# SkateInfoView.net
KiCad netlist of a schematic drawn in Altium Designer
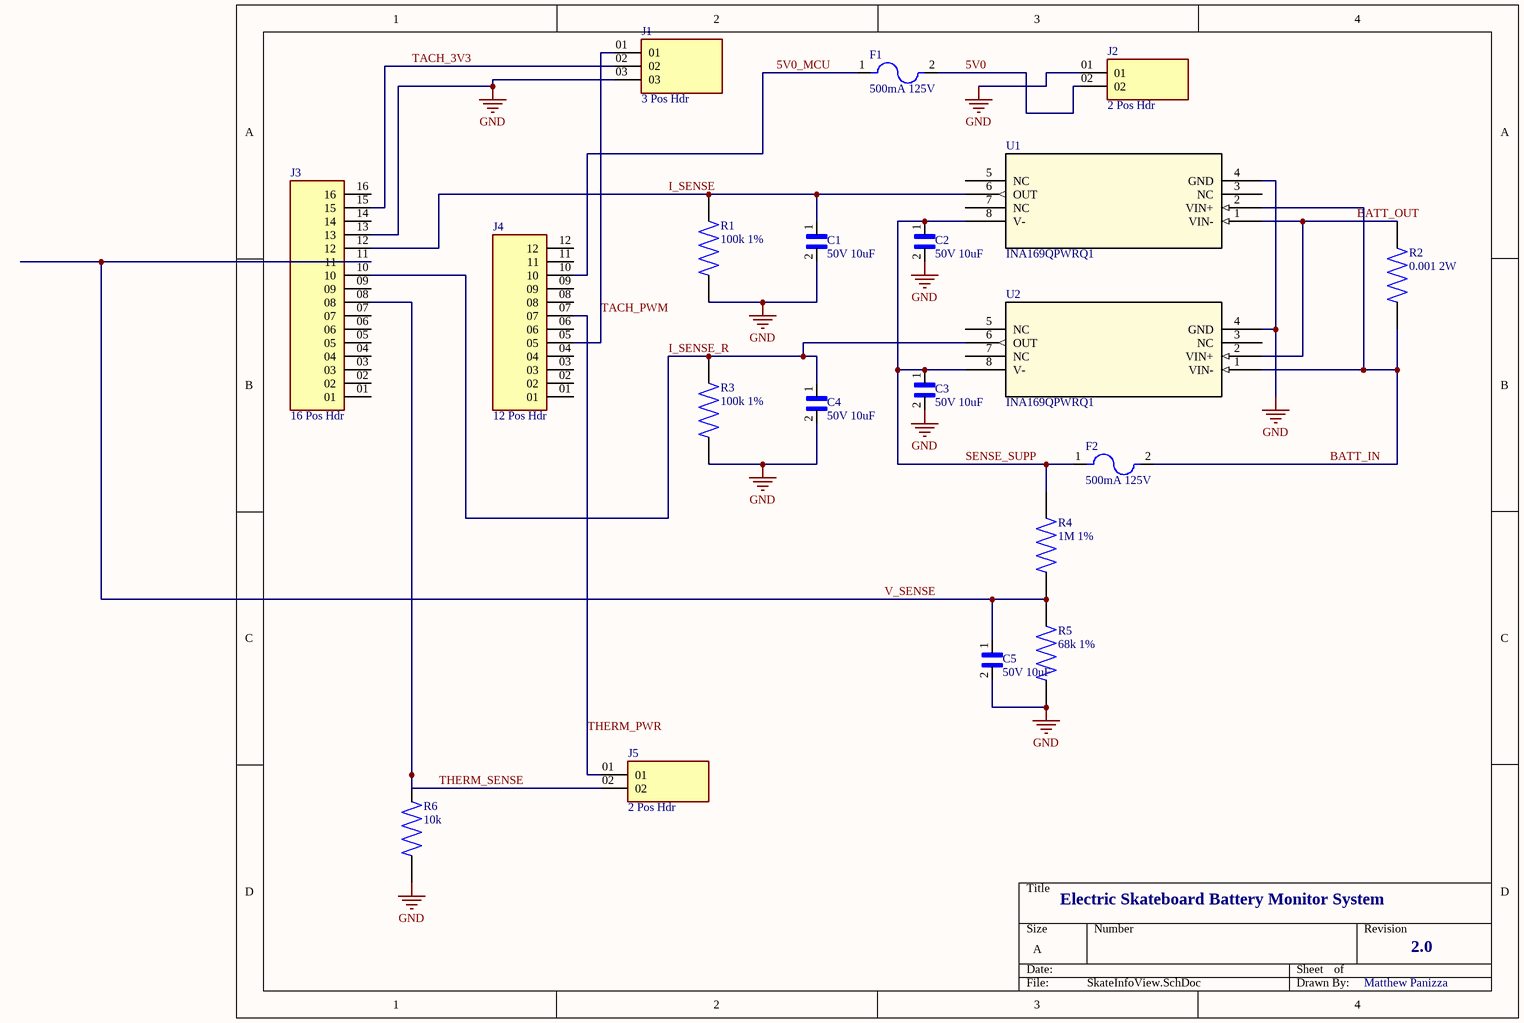
[diagram p0: SkateInfoView.SchDoc]

(export (version "E")
  (design (tool "Eeschema 10.0.6"))
  (components
    (comp (ref "C1")
      (value "50V 10uF")
      (footprint "GRT31CR61H106ME01L:CAP3216X125N")
      (description "1206 10 uF 50 V Â±20% Tolerance X5R Multilayer Ceramic Capacitor")
      (fields
        (field (name "MP") "GRT31CR61H106ME01L")
        (field (name "MF") "{'manufacturer': u'Murata Electronics'}")
      )
      (libsource (lib "GRT31CR61H106ME01L") (part "GRT31CR61H106ME01L"))
    )
    (comp (ref "C2")
      (value "50V 10uF")
      (footprint "GRT31CR61H106ME01L:CAP3216X125N")
      (description "1206 10 uF 50 V Â±20% Tolerance X5R Multilayer Ceramic Capacitor")
      (fields
        (field (name "MP") "GRT31CR61H106ME01L")
        (field (name "MF") "{'manufacturer': u'Murata Electronics'}")
      )
      (libsource (lib "GRT31CR61H106ME01L") (part "GRT31CR61H106ME01L"))
    )
    (comp (ref "C3")
      (value "50V 10uF")
      (footprint "GRT31CR61H106ME01L:CAP3216X125N")
      (description "1206 10 uF 50 V Â±20% Tolerance X5R Multilayer Ceramic Capacitor")
      (fields
        (field (name "MP") "GRT31CR61H106ME01L")
        (field (name "MF") "{'manufacturer': u'Murata Electronics'}")
      )
      (libsource (lib "GRT31CR61H106ME01L") (part "GRT31CR61H106ME01L"))
    )
    (comp (ref "C4")
      (value "50V 10uF")
      (footprint "GRT31CR61H106ME01L:CAP3216X125N")
      (description "1206 10 uF 50 V Â±20% Tolerance X5R Multilayer Ceramic Capacitor")
      (fields
        (field (name "MP") "GRT31CR61H106ME01L")
        (field (name "MF") "{'manufacturer': u'Murata Electronics'}")
      )
      (libsource (lib "GRT31CR61H106ME01L") (part "GRT31CR61H106ME01L"))
    )
    (comp (ref "C5")
      (value "50V 10uF")
      (footprint "GRT31CR61H106ME01L:CAP3216X125N")
      (description "1206 10 uF 50 V Â±20% Tolerance X5R Multilayer Ceramic Capacitor")
      (fields
        (field (name "MP") "GRT31CR61H106ME01L")
        (field (name "MF") "{'manufacturer': u'Murata Electronics'}")
      )
      (libsource (lib "GRT31CR61H106ME01L") (part "GRT31CR61H106ME01L"))
    )
    (comp (ref "F1")
      (value "500mA 125V")
      (footprint "C1Q-500:FUSC3215X78N")
      (fields (field (name "MP") "C1Q-500") (field (name "MF") "{'manufacturer': u'Bel Fuse'}"))
      (libsource (lib "C1Q-500") (part "C1Q-500"))
    )
    (comp (ref "F2")
      (value "500mA 125V")
      (footprint "C1Q-500:FUSC3215X78N")
      (fields (field (name "MP") "C1Q-500") (field (name "MF") "{'manufacturer': u'Bel Fuse'}"))
      (libsource (lib "C1Q-500") (part "C1Q-500"))
    )
    (comp (ref "J1")
      (value "3 Pos Hdr")
      (footprint "SSQ-103-02-T-S-RA:SAMTEC_SSQ-103-02-T-S-RA")
      (fields (field (name "MP") "SSQ-103-02-T-S-RA") (field (name "MF") "{'manufacturer': u'Samtec'}"))
      (libsource (lib "SSQ-103-02-T-S-RA") (part "SSQ-103-02-T-S-RA"))
    )
    (comp (ref "J2")
      (value "2 Pos Hdr")
      (footprint "SSQ10202TSRA:SAMTEC_SSQ-102-02-T-S-RA")
      (fields (field (name "MP") "SSQ-102-02-T-S-RA") (field (name "MF") "{'manufacturer': u'Samtec'}"))
      (libsource (lib "SSQ10202TSRA") (part "SSQ-102-02-T-S-RA"))
    )
    (comp (ref "J3")
      (value "16 Pos Hdr")
      (footprint "SSW-116-01-L-S:SAMTEC_SSW-116-XX-X-S")
      (fields (field (name "MP") "SSW-116-XX-X-S") (field (name "MF") "{'manufacturer': u'Samtec'}"))
      (libsource (lib "SSW-116-01-L-S") (part "SSW-116-XX-X-S"))
    )
    (comp (ref "J4")
      (value "12 Pos Hdr")
      (footprint "SSW-112-01-L-S:SAMTEC_SSW-112-01-X-S")
      (description "CONN RCPT 12POS 0.1 GOLD PCB")
      (fields (field (name "MP") "SSW-112-01-X-S") (field (name "MF") "{'manufacturer': u'Samtec'}"))
      (libsource (lib "SSW-112-01-L-S") (part "SSW-112-01-X-S"))
    )
    (comp (ref "J5")
      (value "2 Pos Hdr")
      (footprint "SSQ10202TSRA:SAMTEC_SSQ-102-02-T-S-RA")
      (fields (field (name "MP") "SSQ-102-02-T-S-RA") (field (name "MF") "{'manufacturer': u'Samtec'}"))
      (libsource (lib "SSQ10202TSRA") (part "SSQ-102-02-T-S-RA"))
    )
    (comp (ref "R1")
      (value "100k 1%")
      (footprint "CRG0805F100K:RESC2012X65N")
      (description "CRG0805 1% 100K")
      (fields (field (name "MP") "CRG0805F100K") (field (name "MF") "{'manufacturer': u'TE Connectivity'}"))
      (libsource (lib "CRG0805F100K") (part "CRG0805F100K"))
    )
    (comp (ref "R2")
      (value "0.001 2W")
      (footprint "CRE2512-FZ-R001E-3:RESC6432X90N")
      (fields (field (name "MP") "CRE2512-FZ-R001E-3") (field (name "MF") "{'manufacturer': u'Bourns Inc.'}"))
      (libsource (lib "CRE2512-FZ-R001E-3") (part "CRE2512-FZ-R001E-3"))
    )
    (comp (ref "R3")
      (value "100k 1%")
      (footprint "CRG0805F100K:RESC2012X65N")
      (description "CRG0805 1% 100K")
      (fields (field (name "MP") "CRG0805F100K") (field (name "MF") "{'manufacturer': u'TE Connectivity'}"))
      (libsource (lib "CRG0805F100K") (part "CRG0805F100K"))
    )
    (comp (ref "R4")
      (value "1M 1%")
      (footprint "CRG1206F1M0:RESC3115X65N")
      (description "CRG1206 1% 1M0")
      (fields (field (name "MP") "CRG1206F1M0") (field (name "MF") "{'manufacturer': u'TE Connectivity'}"))
      (libsource (lib "CRG1206F1M0") (part "CRG1206F1M0"))
    )
    (comp (ref "R5")
      (value "68k 1%")
      (footprint "CRGCQ1206F68K:RESC3115X65N")
      (description "Fixed Resistor CRGCQ 1206 68K 1%")
      (fields (field (name "MP") "CRGCQ1206F68K") (field (name "MF") "{'manufacturer': u'TE Connectivity'}"))
      (libsource (lib "CRGCQ1206F68K") (part "CRGCQ1206F68K"))
    )
    (comp (ref "R6")
      (value "10k")
      (footprint "CRGCQ0805J10K:RESC2012X65N")
      (description "Fixed Resistor CRGCQ 0805 10K 5%")
      (fields (field (name "MP") "CRGCQ0805J10K") (field (name "MF") "{'manufacturer': u'TE Connectivity'}"))
      (libsource (lib "CRGCQ0805J10K") (part "CRGCQ0805J10K"))
    )
    (comp (ref "U1")
      (value "INA169QPWRQ1")
      (footprint "PW8")
      (description "No Description Available")
      (fields (field (name "COPYRIGHT") "Copyright (C) 2021 Ultra Librarian. All rights reserved."))
      (libsource (lib "INA169QPWRQ1") (part "INA169QPWRQ1"))
    )
    (comp (ref "U2")
      (value "INA169QPWRQ1")
      (footprint "PW8")
      (description "No Description Available")
      (fields (field (name "COPYRIGHT") "Copyright (C) 2021 Ultra Librarian. All rights reserved."))
      (libsource (lib "INA169QPWRQ1") (part "INA169QPWRQ1"))
    )
  )
  (nets
    (net (code "1") (name "/5V0") (class "Default")
      (node (ref "F1") (pin "2") (pinfunction "2_2") (pintype "passive"))
      (node (ref "J2") (pin "02") (pinfunction "02_02") (pintype "passive"))
    )
    (net (code "2") (name "/5V0_MCU") (class "Default")
      (node (ref "F1") (pin "1") (pinfunction "1_1") (pintype "passive"))
      (node (ref "J4") (pin "10") (pinfunction "10_10") (pintype "passive"))
    )
    (net (code "3") (name "/BATT_IN") (class "Default")
      (node (ref "F2") (pin "2") (pinfunction "2_2") (pintype "passive"))
      (node (ref "R2") (pin "1") (pinfunction "1_1") (pintype "passive"))
      (node (ref "U1") (pin "2") (pinfunction "VIN+_2") (pintype "input"))
      (node (ref "U2") (pin "1") (pinfunction "VIN-_1") (pintype "input"))
    )
    (net (code "4") (name "/BATT_OUT") (class "Default")
      (node (ref "R2") (pin "2") (pinfunction "2_2") (pintype "passive"))
      (node (ref "U1") (pin "1") (pinfunction "VIN-_1") (pintype "input"))
      (node (ref "U2") (pin "2") (pinfunction "VIN+_2") (pintype "input"))
    )
    (net (code "5") (name "/I_SENSE") (class "Default")
      (node (ref "C1") (pin "1") (pinfunction "1_1") (pintype "passive"))
      (node (ref "J3") (pin "12") (pinfunction "12_12") (pintype "passive"))
      (node (ref "R1") (pin "2") (pinfunction "2_2") (pintype "passive"))
      (node (ref "U1") (pin "6") (pinfunction "OUT_6") (pintype "output"))
    )
    (net (code "6") (name "/I_SENSE_R") (class "Default")
      (node (ref "C4") (pin "1") (pinfunction "1_1") (pintype "passive"))
      (node (ref "J3") (pin "10") (pinfunction "10_10") (pintype "passive"))
      (node (ref "R3") (pin "2") (pinfunction "2_2") (pintype "passive"))
      (node (ref "U2") (pin "6") (pinfunction "OUT_6") (pintype "output"))
    )
    (net (code "7") (name "/SENSE_SUPP") (class "Default")
      (node (ref "C2") (pin "1") (pinfunction "1_1") (pintype "passive"))
      (node (ref "C3") (pin "1") (pinfunction "1_1") (pintype "passive"))
      (node (ref "F2") (pin "1") (pinfunction "1_1") (pintype "passive"))
      (node (ref "R4") (pin "2") (pinfunction "2_2") (pintype "passive"))
      (node (ref "U1") (pin "8") (pinfunction "V-_8") (pintype "power_in"))
      (node (ref "U2") (pin "8") (pinfunction "V-_8") (pintype "power_in"))
    )
    (net (code "8") (name "/TACH_3V3") (class "Default")
      (node (ref "J1") (pin "02") (pinfunction "02_02") (pintype "passive"))
      (node (ref "J3") (pin "15") (pinfunction "15_15") (pintype "passive"))
    )
    (net (code "9") (name "/TACH_PWM") (class "Default")
      (node (ref "J1") (pin "01") (pinfunction "01_01") (pintype "passive"))
      (node (ref "J4") (pin "05") (pinfunction "05_05") (pintype "passive"))
    )
    (net (code "10") (name "/THERM_PWR") (class "Default")
      (node (ref "J4") (pin "07") (pinfunction "07_07") (pintype "passive"))
      (node (ref "J5") (pin "01") (pinfunction "01_01") (pintype "passive"))
    )
    (net (code "11") (name "/THERM_SENSE") (class "Default")
      (node (ref "J3") (pin "08") (pinfunction "08_08") (pintype "passive"))
      (node (ref "J5") (pin "02") (pinfunction "02_02") (pintype "passive"))
      (node (ref "R6") (pin "2") (pinfunction "2_2") (pintype "passive"))
    )
    (net (code "12") (name "/V_SENSE") (class "Default")
      (node (ref "C5") (pin "1") (pinfunction "1_1") (pintype "passive"))
      (node (ref "J3") (pin "11") (pinfunction "11_11") (pintype "passive"))
      (node (ref "R4") (pin "1") (pinfunction "1_1") (pintype "passive"))
      (node (ref "R5") (pin "2") (pinfunction "2_2") (pintype "passive"))
    )
    (net (code "13") (name "GND") (class "Default")
      (node (ref "C1") (pin "2") (pinfunction "2_2") (pintype "passive"))
      (node (ref "C2") (pin "2") (pinfunction "2_2") (pintype "passive"))
      (node (ref "C3") (pin "2") (pinfunction "2_2") (pintype "passive"))
      (node (ref "C4") (pin "2") (pinfunction "2_2") (pintype "passive"))
      (node (ref "C5") (pin "2") (pinfunction "2_2") (pintype "passive"))
      (node (ref "J1") (pin "03") (pinfunction "03_03") (pintype "passive"))
      (node (ref "J2") (pin "01") (pinfunction "01_01") (pintype "passive"))
      (node (ref "J3") (pin "13") (pinfunction "13_13") (pintype "passive"))
      (node (ref "R1") (pin "1") (pinfunction "1_1") (pintype "passive"))
      (node (ref "R3") (pin "1") (pinfunction "1_1") (pintype "passive"))
      (node (ref "R5") (pin "1") (pinfunction "1_1") (pintype "passive"))
      (node (ref "R6") (pin "1") (pinfunction "1_1") (pintype "passive"))
      (node (ref "U1") (pin "4") (pinfunction "GND_4") (pintype "power_in"))
      (node (ref "U2") (pin "4") (pinfunction "GND_4") (pintype "power_in"))
    )
    (net (code "14") (name "unconnected-(J3-Pad01)") (class "Default")
      (node (ref "J3") (pin "01") (pinfunction "01_01") (pintype "passive"))
    )
    (net (code "15") (name "unconnected-(J3-Pad02)") (class "Default")
      (node (ref "J3") (pin "02") (pinfunction "02_02") (pintype "passive"))
    )
    (net (code "16") (name "unconnected-(J3-Pad03)") (class "Default")
      (node (ref "J3") (pin "03") (pinfunction "03_03") (pintype "passive"))
    )
    (net (code "17") (name "unconnected-(J3-Pad04)") (class "Default")
      (node (ref "J3") (pin "04") (pinfunction "04_04") (pintype "passive"))
    )
    (net (code "18") (name "unconnected-(J3-Pad05)") (class "Default")
      (node (ref "J3") (pin "05") (pinfunction "05_05") (pintype "passive"))
    )
    (net (code "19") (name "unconnected-(J3-Pad06)") (class "Default")
      (node (ref "J3") (pin "06") (pinfunction "06_06") (pintype "passive"))
    )
    (net (code "20") (name "unconnected-(J3-Pad07)") (class "Default")
      (node (ref "J3") (pin "07") (pinfunction "07_07") (pintype "passive"))
    )
    (net (code "21") (name "unconnected-(J3-Pad09)") (class "Default")
      (node (ref "J3") (pin "09") (pinfunction "09_09") (pintype "passive"))
    )
    (net (code "22") (name "unconnected-(J3-Pad14)") (class "Default")
      (node (ref "J3") (pin "14") (pinfunction "14_14") (pintype "passive"))
    )
    (net (code "23") (name "unconnected-(J3-Pad16)") (class "Default")
      (node (ref "J3") (pin "16") (pinfunction "16_16") (pintype "passive"))
    )
    (net (code "24") (name "unconnected-(J4-Pad01)") (class "Default")
      (node (ref "J4") (pin "01") (pinfunction "01_01") (pintype "passive"))
    )
    (net (code "25") (name "unconnected-(J4-Pad02)") (class "Default")
      (node (ref "J4") (pin "02") (pinfunction "02_02") (pintype "passive"))
    )
    (net (code "26") (name "unconnected-(J4-Pad03)") (class "Default")
      (node (ref "J4") (pin "03") (pinfunction "03_03") (pintype "passive"))
    )
    (net (code "27") (name "unconnected-(J4-Pad04)") (class "Default")
      (node (ref "J4") (pin "04") (pinfunction "04_04") (pintype "passive"))
    )
    (net (code "28") (name "unconnected-(J4-Pad06)") (class "Default")
      (node (ref "J4") (pin "06") (pinfunction "06_06") (pintype "passive"))
    )
    (net (code "29") (name "unconnected-(J4-Pad08)") (class "Default")
      (node (ref "J4") (pin "08") (pinfunction "08_08") (pintype "passive"))
    )
    (net (code "30") (name "unconnected-(J4-Pad09)") (class "Default")
      (node (ref "J4") (pin "09") (pinfunction "09_09") (pintype "passive"))
    )
    (net (code "31") (name "unconnected-(J4-Pad11)") (class "Default")
      (node (ref "J4") (pin "11") (pinfunction "11_11") (pintype "passive"))
    )
    (net (code "32") (name "unconnected-(J4-Pad12)") (class "Default")
      (node (ref "J4") (pin "12") (pinfunction "12_12") (pintype "passive"))
    )
    (net (code "33") (name "unconnected-(U1-NC-Pad3)") (class "Default")
      (node (ref "U1") (pin "3") (pinfunction "NC_3") (pintype "passive"))
    )
    (net (code "34") (name "unconnected-(U1-NC-Pad5)") (class "Default")
      (node (ref "U1") (pin "5") (pinfunction "NC_5") (pintype "passive"))
    )
    (net (code "35") (name "unconnected-(U1-NC-Pad7)") (class "Default")
      (node (ref "U1") (pin "7") (pinfunction "NC_7") (pintype "passive"))
    )
    (net (code "36") (name "unconnected-(U2-NC-Pad3)") (class "Default")
      (node (ref "U2") (pin "3") (pinfunction "NC_3") (pintype "passive"))
    )
    (net (code "37") (name "unconnected-(U2-NC-Pad5)") (class "Default")
      (node (ref "U2") (pin "5") (pinfunction "NC_5") (pintype "passive"))
    )
    (net (code "38") (name "unconnected-(U2-NC-Pad7)") (class "Default")
      (node (ref "U2") (pin "7") (pinfunction "NC_7") (pintype "passive"))
    )
  )
)
